# meter.net
KiCad netlist of a schematic drawn in EAGLE
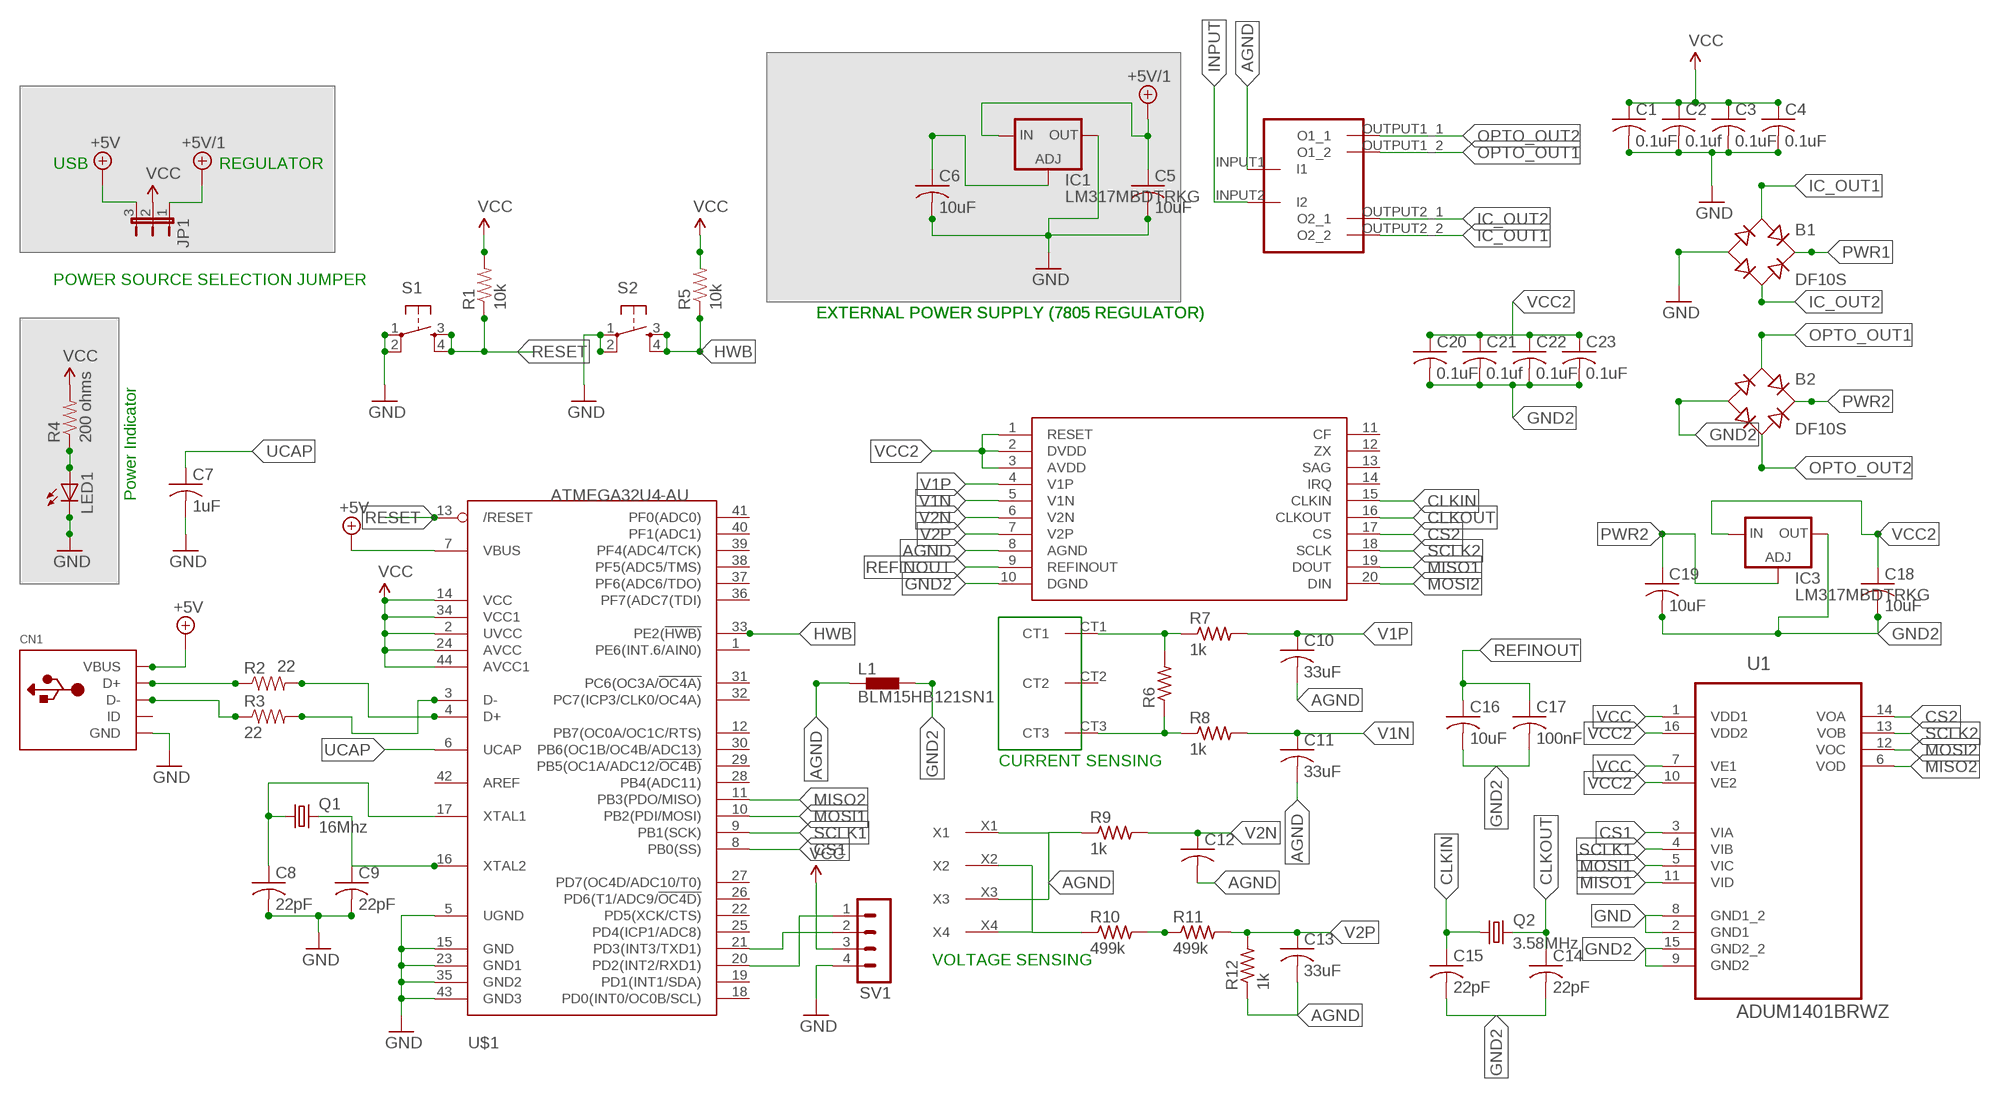
[diagram p0: schematic, sheet 1]

(export (version "E")
  (design (tool "Eeschema 10.0.6"))
  (components
    (comp (ref "B1")
      (value "DF10S")
      (footprint "eagle-import:DFS")
      (libsource (lib "eagle-import") (part "DFS10"))
    )
    (comp (ref "B2")
      (value "DF10S")
      (footprint "eagle-import:DFS")
      (libsource (lib "eagle-import") (part "DFS10"))
    )
    (comp (ref "C1")
      (value "0.1uF")
      (footprint "eagle-import:C0603")
      (libsource (lib "eagle-import") (part "C-USC0603"))
    )
    (comp (ref "C2")
      (value "0.1uf")
      (footprint "eagle-import:C0603")
      (libsource (lib "eagle-import") (part "C-USC0603"))
    )
    (comp (ref "C3")
      (value "0.1uF")
      (footprint "eagle-import:C0603")
      (libsource (lib "eagle-import") (part "C-USC0603"))
    )
    (comp (ref "C4")
      (value "0.1uF")
      (footprint "eagle-import:C0603")
      (libsource (lib "eagle-import") (part "C-USC0603"))
    )
    (comp (ref "C5")
      (value "10uF")
      (footprint "eagle-import:C0603")
      (libsource (lib "eagle-import") (part "C-USC0603"))
    )
    (comp (ref "C6")
      (value "10uF")
      (footprint "eagle-import:C0603")
      (libsource (lib "eagle-import") (part "C-USC0603"))
    )
    (comp (ref "C7")
      (value "1uF")
      (footprint "eagle-import:C0603")
      (libsource (lib "eagle-import") (part "C-USC0603"))
    )
    (comp (ref "C8")
      (value "22pF")
      (footprint "eagle-import:C0603")
      (libsource (lib "eagle-import") (part "C-USC0603"))
    )
    (comp (ref "C9")
      (value "22pF")
      (footprint "eagle-import:C0603")
      (libsource (lib "eagle-import") (part "C-USC0603"))
    )
    (comp (ref "C10")
      (value "33uF")
      (footprint "eagle-import:C0603")
      (libsource (lib "eagle-import") (part "C-USC0603"))
    )
    (comp (ref "C11")
      (value "33uF")
      (footprint "eagle-import:C0603")
      (libsource (lib "eagle-import") (part "C-USC0603"))
    )
    (comp (ref "C12")
      (value "C-USC0603")
      (footprint "eagle-import:C0603")
      (libsource (lib "eagle-import") (part "C-USC0603"))
    )
    (comp (ref "C13")
      (value "33uF")
      (footprint "eagle-import:C0603")
      (libsource (lib "eagle-import") (part "C-USC0603"))
    )
    (comp (ref "C14")
      (value "22pF")
      (footprint "eagle-import:C0603")
      (libsource (lib "eagle-import") (part "C-USC0603"))
    )
    (comp (ref "C15")
      (value "22pF")
      (footprint "eagle-import:C0603")
      (libsource (lib "eagle-import") (part "C-USC0603"))
    )
    (comp (ref "C16")
      (value "10uF")
      (footprint "eagle-import:C0603")
      (libsource (lib "eagle-import") (part "C-USC0603"))
    )
    (comp (ref "C17")
      (value "100nF")
      (footprint "eagle-import:C0603")
      (libsource (lib "eagle-import") (part "C-USC0603"))
    )
    (comp (ref "C18")
      (value "10uF")
      (footprint "eagle-import:C0603")
      (libsource (lib "eagle-import") (part "C-USC0603"))
    )
    (comp (ref "C19")
      (value "10uF")
      (footprint "eagle-import:C0603")
      (libsource (lib "eagle-import") (part "C-USC0603"))
    )
    (comp (ref "C20")
      (value "0.1uF")
      (footprint "eagle-import:C0603")
      (libsource (lib "eagle-import") (part "C-USC0603"))
    )
    (comp (ref "C21")
      (value "0.1uf")
      (footprint "eagle-import:C0603")
      (libsource (lib "eagle-import") (part "C-USC0603"))
    )
    (comp (ref "C22")
      (value "0.1uF")
      (footprint "eagle-import:C0603")
      (libsource (lib "eagle-import") (part "C-USC0603"))
    )
    (comp (ref "C23")
      (value "0.1uF")
      (footprint "eagle-import:C0603")
      (libsource (lib "eagle-import") (part "C-USC0603"))
    )
    (comp (ref "CN1")
      (value "USBMINIB")
      (footprint "eagle-import:USB-MINIB")
      (libsource (lib "eagle-import") (part "USBMINIB"))
    )
    (comp (ref "IC1")
      (value "LM317MBDTRKG")
      (footprint "eagle-import:DPACK")
      (libsource (lib "eagle-import") (part "LM317?MBDTRKG"))
    )
    (comp (ref "IC3")
      (value "LM317MBDTRKG")
      (footprint "eagle-import:DPACK")
      (libsource (lib "eagle-import") (part "LM317?MBDTRKG"))
    )
    (comp (ref "JP1")
      (value "JP2E")
      (footprint "eagle-import:JP2")
      (libsource (lib "eagle-import") (part "JP2E"))
    )
    (comp (ref "L1")
      (value "BLM15HB121SN1")
      (footprint "eagle-import:0402")
      (libsource (lib "eagle-import") (part "BLM15HB121SN1"))
    )
    (comp (ref "LED1")
      (value "LEDCHIP-LED0805")
      (footprint "eagle-import:CHIP-LED0805")
      (libsource (lib "eagle-import") (part "LEDCHIP-LED0805"))
    )
    (comp (ref "Q1")
      (value "16Mhz")
      (footprint "eagle-import:CSM-7X-DU")
      (libsource (lib "eagle-import") (part "CSM-7X-DU"))
    )
    (comp (ref "Q2")
      (value "3.58MHz")
      (footprint "eagle-import:CSM-7X-DU")
      (libsource (lib "eagle-import") (part "CSM-7X-DU"))
    )
    (comp (ref "R1")
      (value "10k")
      (footprint "eagle-import:0603-RES")
      (libsource (lib "eagle-import") (part "RESISTOR0603-RES"))
    )
    (comp (ref "R2")
      (value "22")
      (footprint "eagle-import:0603-RES")
      (libsource (lib "eagle-import") (part "RESISTOR0603-RES"))
    )
    (comp (ref "R3")
      (value "22")
      (footprint "eagle-import:0603-RES")
      (libsource (lib "eagle-import") (part "RESISTOR0603-RES"))
    )
    (comp (ref "R4")
      (value "200 ohms")
      (footprint "eagle-import:0603-RES")
      (libsource (lib "eagle-import") (part "RESISTOR0603-RES"))
    )
    (comp (ref "R5")
      (value "10k")
      (footprint "eagle-import:0603-RES")
      (libsource (lib "eagle-import") (part "RESISTOR0603-RES"))
    )
    (comp (ref "R6")
      (value "R-US_R0603")
      (footprint "eagle-import:R0603")
      (libsource (lib "eagle-import") (part "R-US_R0603"))
    )
    (comp (ref "R7")
      (value "1k")
      (footprint "eagle-import:R0603")
      (libsource (lib "eagle-import") (part "R-US_R0603"))
    )
    (comp (ref "R8")
      (value "1k")
      (footprint "eagle-import:R0603")
      (libsource (lib "eagle-import") (part "R-US_R0603"))
    )
    (comp (ref "R9")
      (value "1k")
      (footprint "eagle-import:R0603")
      (libsource (lib "eagle-import") (part "R-US_R0603"))
    )
    (comp (ref "R10")
      (value "499k")
      (footprint "eagle-import:R0603")
      (libsource (lib "eagle-import") (part "R-US_R0603"))
    )
    (comp (ref "R11")
      (value "499k")
      (footprint "eagle-import:R0603")
      (libsource (lib "eagle-import") (part "R-US_R0603"))
    )
    (comp (ref "R12")
      (value "1k")
      (footprint "eagle-import:R0603")
      (libsource (lib "eagle-import") (part "R-US_R0603"))
    )
    (comp (ref "S1")
      (value "TAC_SWITCHSMD")
      (footprint "eagle-import:TACTILE_SWITCH_SMD")
      (libsource (lib "eagle-import") (part "TAC_SWITCHSMD"))
    )
    (comp (ref "S2")
      (value "TAC_SWITCHSMD")
      (footprint "eagle-import:TACTILE_SWITCH_SMD")
      (libsource (lib "eagle-import") (part "TAC_SWITCHSMD"))
    )
    (comp (ref "SV1")
      (value "MA04-1")
      (footprint "eagle-import:MA04-1")
      (libsource (lib "eagle-import") (part "MA04-1"))
    )
    (comp (ref "U$1")
      (value "ATMEGA32U4-AU")
      (footprint "eagle-import:TQFP44")
      (libsource (lib "eagle-import") (part "ATMEGA32U4-AU"))
    )
    (comp (ref "U$2")
      (value "ADE7753")
      (footprint "eagle-import:SSOP20")
      (libsource (lib "eagle-import") (part "ADE7753"))
    )
    (comp (ref "U$3")
      (value "CT")
      (footprint "eagle-import:CT1075")
      (libsource (lib "eagle-import") (part "CT"))
    )
    (comp (ref "U$4")
      (value "PCB-TRANS")
      (footprint "eagle-import:PCB-TRANS")
      (libsource (lib "eagle-import") (part "PCB-TRANS"))
    )
    (comp (ref "U$6")
      (value "SCREWTERMINAL4_9.53")
      (footprint "eagle-import:SCREWTERMINAL4_9.53")
      (libsource (lib "eagle-import") (part "SCREWTERMINAL4_9.53"))
    )
    (comp (ref "U1")
      (value "ADUM1401BRWZ")
      (footprint "eagle-import:SOIC127P1032X265-16N")
      (libsource (lib "eagle-import") (part "ADUM1401BRWZ"))
    )
  )
  (nets
    (net (code "1") (name "+5V") (class "Default")
      (node (ref "CN1") (pin "VBUS") (pinfunction "VBUS_VBUS") (pintype "power_in"))
      (node (ref "JP1") (pin "3") (pinfunction "3_3") (pintype "passive"))
      (node (ref "U$1") (pin "7") (pinfunction "VBUS_7") (pintype "bidirectional"))
    )
    (net (code "2") (name "+5V{slash}1") (class "Default")
      (node (ref "C5") (pin "1") (pinfunction "1_1") (pintype "passive"))
      (node (ref "IC1") (pin "3") (pinfunction "IN_3") (pintype "input"))
      (node (ref "JP1") (pin "1") (pinfunction "1_1") (pintype "passive"))
    )
    (net (code "3") (name "AGND") (class "Default")
      (node (ref "C10") (pin "2") (pinfunction "2_2") (pintype "passive"))
      (node (ref "C11") (pin "2") (pinfunction "2_2") (pintype "passive"))
      (node (ref "C12") (pin "2") (pinfunction "2_2") (pintype "passive"))
      (node (ref "C13") (pin "2") (pinfunction "2_2") (pintype "passive"))
      (node (ref "L1") (pin "1") (pinfunction "1_1") (pintype "passive"))
      (node (ref "R12") (pin "1") (pinfunction "1_1") (pintype "passive"))
      (node (ref "R9") (pin "1") (pinfunction "1_1") (pintype "passive"))
      (node (ref "U$2") (pin "8") (pinfunction "AGND_8") (pintype "bidirectional"))
      (node (ref "U$4") (pin "INPUT1") (pinfunction "I1_INPUT1") (pintype "bidirectional"))
      (node (ref "U$6") (pin "X1") (pinfunction "X1_X1") (pintype "bidirectional"))
      (node (ref "U$6") (pin "X3") (pinfunction "X3_X3") (pintype "bidirectional"))
    )
    (net (code "4") (name "CLKIN") (class "Default")
      (node (ref "C15") (pin "1") (pinfunction "1_1") (pintype "passive"))
      (node (ref "Q2") (pin "1") (pinfunction "1_1") (pintype "passive"))
      (node (ref "U$2") (pin "15") (pinfunction "CLKIN_15") (pintype "bidirectional"))
    )
    (net (code "5") (name "CLKOUT") (class "Default")
      (node (ref "C14") (pin "1") (pinfunction "1_1") (pintype "passive"))
      (node (ref "Q2") (pin "2") (pinfunction "2_2") (pintype "passive"))
      (node (ref "U$2") (pin "16") (pinfunction "CLKOUT_16") (pintype "bidirectional"))
    )
    (net (code "6") (name "CS1") (class "Default")
      (node (ref "U$1") (pin "8") (pinfunction "PB0(SS)_8") (pintype "bidirectional"))
      (node (ref "U1") (pin "3") (pinfunction "VIA_3") (pintype "input"))
    )
    (net (code "7") (name "CS2") (class "Default")
      (node (ref "U$2") (pin "17") (pinfunction "CS_17") (pintype "bidirectional"))
      (node (ref "U1") (pin "14") (pinfunction "VOA_14") (pintype "output"))
    )
    (net (code "8") (name "GND") (class "Default")
      (node (ref "B1") (pin "-") (pinfunction "-_-") (pintype "passive"))
      (node (ref "C1") (pin "2") (pinfunction "2_2") (pintype "passive"))
      (node (ref "C2") (pin "2") (pinfunction "2_2") (pintype "passive"))
      (node (ref "C3") (pin "2") (pinfunction "2_2") (pintype "passive"))
      (node (ref "C4") (pin "2") (pinfunction "2_2") (pintype "passive"))
      (node (ref "C5") (pin "2") (pinfunction "2_2") (pintype "passive"))
      (node (ref "C6") (pin "2") (pinfunction "2_2") (pintype "passive"))
      (node (ref "C7") (pin "2") (pinfunction "2_2") (pintype "passive"))
      (node (ref "C8") (pin "2") (pinfunction "2_2") (pintype "passive"))
      (node (ref "C9") (pin "2") (pinfunction "2_2") (pintype "passive"))
      (node (ref "CN1") (pin "GND") (pinfunction "GND_GND") (pintype "power_in"))
      (node (ref "IC1") (pin "4") (pinfunction "OUT_4") (pintype "passive"))
      (node (ref "LED1") (pin "C") (pinfunction "C_C") (pintype "passive"))
      (node (ref "S1") (pin "1") (pinfunction "1_1") (pintype "passive"))
      (node (ref "S1") (pin "2") (pinfunction "2_2") (pintype "passive"))
      (node (ref "S2") (pin "1") (pinfunction "1_1") (pintype "passive"))
      (node (ref "S2") (pin "2") (pinfunction "2_2") (pintype "passive"))
      (node (ref "SV1") (pin "4") (pinfunction "4_4") (pintype "passive"))
      (node (ref "U$1") (pin "15") (pinfunction "GND_15") (pintype "bidirectional"))
      (node (ref "U$1") (pin "23") (pinfunction "GND1_23") (pintype "bidirectional"))
      (node (ref "U$1") (pin "35") (pinfunction "GND2_35") (pintype "bidirectional"))
      (node (ref "U$1") (pin "43") (pinfunction "GND3_43") (pintype "bidirectional"))
      (node (ref "U$1") (pin "5") (pinfunction "UGND_5") (pintype "bidirectional"))
      (node (ref "U1") (pin "2") (pinfunction "GND1_2") (pintype "passive"))
      (node (ref "U1") (pin "8") (pinfunction "GND1_2_8") (pintype "passive"))
    )
    (net (code "9") (name "GND2") (class "Default")
      (node (ref "B2") (pin "-") (pinfunction "-_-") (pintype "passive"))
      (node (ref "C14") (pin "2") (pinfunction "2_2") (pintype "passive"))
      (node (ref "C15") (pin "2") (pinfunction "2_2") (pintype "passive"))
      (node (ref "C16") (pin "2") (pinfunction "2_2") (pintype "passive"))
      (node (ref "C17") (pin "2") (pinfunction "2_2") (pintype "passive"))
      (node (ref "C18") (pin "2") (pinfunction "2_2") (pintype "passive"))
      (node (ref "C19") (pin "2") (pinfunction "2_2") (pintype "passive"))
      (node (ref "C20") (pin "2") (pinfunction "2_2") (pintype "passive"))
      (node (ref "C21") (pin "2") (pinfunction "2_2") (pintype "passive"))
      (node (ref "C22") (pin "2") (pinfunction "2_2") (pintype "passive"))
      (node (ref "C23") (pin "2") (pinfunction "2_2") (pintype "passive"))
      (node (ref "IC3") (pin "4") (pinfunction "OUT_4") (pintype "passive"))
      (node (ref "L1") (pin "2") (pinfunction "2_2") (pintype "passive"))
      (node (ref "U$2") (pin "10") (pinfunction "DGND_10") (pintype "bidirectional"))
      (node (ref "U1") (pin "15") (pinfunction "GND2_2_15") (pintype "passive"))
      (node (ref "U1") (pin "9") (pinfunction "GND2_9") (pintype "passive"))
    )
    (net (code "10") (name "HWB") (class "Default")
      (node (ref "R5") (pin "1") (pinfunction "1_1") (pintype "passive"))
      (node (ref "S2") (pin "3") (pinfunction "3_3") (pintype "passive"))
      (node (ref "S2") (pin "4") (pinfunction "4_4") (pintype "passive"))
      (node (ref "U$1") (pin "33") (pinfunction "PE2(~{HWB})_33") (pintype "bidirectional"))
    )
    (net (code "11") (name "IC_OUT1") (class "Default")
      (node (ref "B1") (pin "AC1") (pinfunction "AC1_AC1") (pintype "passive"))
      (node (ref "U$4") (pin "OUTPUT2_2") (pinfunction "O2_2_OUTPUT2_2") (pintype "bidirectional"))
    )
    (net (code "12") (name "IC_OUT2") (class "Default")
      (node (ref "B1") (pin "AC2") (pinfunction "AC2_AC2") (pintype "passive"))
      (node (ref "U$4") (pin "OUTPUT2_1") (pinfunction "O2_1_OUTPUT2_1") (pintype "bidirectional"))
    )
    (net (code "13") (name "INPUT") (class "Default")
      (node (ref "R10") (pin "1") (pinfunction "1_1") (pintype "passive"))
      (node (ref "U$4") (pin "INPUT2") (pinfunction "I2_INPUT2") (pintype "bidirectional"))
      (node (ref "U$6") (pin "X2") (pinfunction "X2_X2") (pintype "bidirectional"))
      (node (ref "U$6") (pin "X4") (pinfunction "X4_X4") (pintype "bidirectional"))
    )
    (net (code "14") (name "MISO1") (class "Default")
      (node (ref "U$2") (pin "19") (pinfunction "DOUT_19") (pintype "bidirectional"))
      (node (ref "U1") (pin "11") (pinfunction "VID_11") (pintype "input"))
    )
    (net (code "15") (name "MISO2") (class "Default")
      (node (ref "U$1") (pin "11") (pinfunction "PB3(PDO/MISO)_11") (pintype "bidirectional"))
      (node (ref "U1") (pin "6") (pinfunction "VOD_6") (pintype "output"))
    )
    (net (code "16") (name "MOSI1") (class "Default")
      (node (ref "U$1") (pin "10") (pinfunction "PB2(PDI/MOSI)_10") (pintype "bidirectional"))
      (node (ref "U1") (pin "5") (pinfunction "VIC_5") (pintype "input"))
    )
    (net (code "17") (name "MOSI2") (class "Default")
      (node (ref "U$2") (pin "20") (pinfunction "DIN_20") (pintype "bidirectional"))
      (node (ref "U1") (pin "12") (pinfunction "VOC_12") (pintype "output"))
    )
    (net (code "18") (name "Net-(CN1-PadD+)") (class "Default")
      (node (ref "CN1") (pin "D+") (pinfunction "D+_D+") (pintype "bidirectional"))
      (node (ref "R2") (pin "1") (pinfunction "1_1") (pintype "passive"))
    )
    (net (code "19") (name "Net-(CN1-PadD-)") (class "Default")
      (node (ref "CN1") (pin "D-") (pinfunction "D-_D-") (pintype "bidirectional"))
      (node (ref "R3") (pin "1") (pinfunction "1_1") (pintype "passive"))
    )
    (net (code "20") (name "Net-(LED1-PadA)") (class "Default")
      (node (ref "LED1") (pin "A") (pinfunction "A_A") (pintype "passive"))
      (node (ref "R4") (pin "1") (pinfunction "1_1") (pintype "passive"))
    )
    (net (code "21") (name "Net-(R6-Pad1)") (class "Default")
      (node (ref "R6") (pin "1") (pinfunction "1_1") (pintype "passive"))
      (node (ref "R8") (pin "1") (pinfunction "1_1") (pintype "passive"))
      (node (ref "U$3") (pin "CT3") (pinfunction "CT3_CT3") (pintype "bidirectional"))
    )
    (net (code "22") (name "Net-(R6-Pad2)") (class "Default")
      (node (ref "R6") (pin "2") (pinfunction "2_2") (pintype "passive"))
      (node (ref "R7") (pin "1") (pinfunction "1_1") (pintype "passive"))
      (node (ref "U$3") (pin "CT1") (pinfunction "CT1_CT1") (pintype "bidirectional"))
    )
    (net (code "23") (name "Net-(R10-Pad2)") (class "Default")
      (node (ref "R10") (pin "2") (pinfunction "2_2") (pintype "passive"))
      (node (ref "R11") (pin "1") (pinfunction "1_1") (pintype "passive"))
    )
    (net (code "24") (name "Net-(U$1-D+)") (class "Default")
      (node (ref "R2") (pin "2") (pinfunction "2_2") (pintype "passive"))
      (node (ref "U$1") (pin "4") (pinfunction "D+_4") (pintype "bidirectional"))
    )
    (net (code "25") (name "Net-(U$1-D-)") (class "Default")
      (node (ref "R3") (pin "2") (pinfunction "2_2") (pintype "passive"))
      (node (ref "U$1") (pin "3") (pinfunction "D-_3") (pintype "bidirectional"))
    )
    (net (code "26") (name "Net-(U$1-PD2(INT2{slash}RXD1))") (class "Default")
      (node (ref "SV1") (pin "1") (pinfunction "1_1") (pintype "passive"))
      (node (ref "U$1") (pin "20") (pinfunction "PD2(INT2/RXD1)_20") (pintype "bidirectional"))
    )
    (net (code "27") (name "Net-(U$1-PD3(INT3{slash}TXD1))") (class "Default")
      (node (ref "SV1") (pin "2") (pinfunction "2_2") (pintype "passive"))
      (node (ref "U$1") (pin "21") (pinfunction "PD3(INT3/TXD1)_21") (pintype "bidirectional"))
    )
    (net (code "28") (name "Net-(U$1-XTAL1)") (class "Default")
      (node (ref "C8") (pin "1") (pinfunction "1_1") (pintype "passive"))
      (node (ref "Q1") (pin "1") (pinfunction "1_1") (pintype "passive"))
      (node (ref "U$1") (pin "17") (pinfunction "XTAL1_17") (pintype "bidirectional"))
    )
    (net (code "29") (name "Net-(U$1-XTAL2)") (class "Default")
      (node (ref "C9") (pin "1") (pinfunction "1_1") (pintype "passive"))
      (node (ref "Q1") (pin "2") (pinfunction "2_2") (pintype "passive"))
      (node (ref "U$1") (pin "16") (pinfunction "XTAL2_16") (pintype "bidirectional"))
    )
    (net (code "30") (name "OPTO_OUT1") (class "Default")
      (node (ref "B2") (pin "AC1") (pinfunction "AC1_AC1") (pintype "passive"))
      (node (ref "U$4") (pin "OUTPUT1_2") (pinfunction "O1_2_OUTPUT1_2") (pintype "bidirectional"))
    )
    (net (code "31") (name "OPTO_OUT2") (class "Default")
      (node (ref "B2") (pin "AC2") (pinfunction "AC2_AC2") (pintype "passive"))
      (node (ref "U$4") (pin "OUTPUT1_1") (pinfunction "O1_1_OUTPUT1_1") (pintype "bidirectional"))
    )
    (net (code "32") (name "PWR1") (class "Default")
      (node (ref "B1") (pin "+") (pinfunction "+_+") (pintype "passive"))
      (node (ref "C6") (pin "1") (pinfunction "1_1") (pintype "passive"))
      (node (ref "IC1") (pin "1") (pinfunction "ADJ_1") (pintype "input"))
    )
    (net (code "33") (name "PWR2") (class "Default")
      (node (ref "B2") (pin "+") (pinfunction "+_+") (pintype "passive"))
      (node (ref "C19") (pin "1") (pinfunction "1_1") (pintype "passive"))
      (node (ref "IC3") (pin "1") (pinfunction "ADJ_1") (pintype "input"))
    )
    (net (code "34") (name "REFINOUT") (class "Default")
      (node (ref "C16") (pin "1") (pinfunction "1_1") (pintype "passive"))
      (node (ref "C17") (pin "1") (pinfunction "1_1") (pintype "passive"))
      (node (ref "U$2") (pin "9") (pinfunction "REFINOUT_9") (pintype "bidirectional"))
    )
    (net (code "35") (name "RESET") (class "Default")
      (node (ref "R1") (pin "1") (pinfunction "1_1") (pintype "passive"))
      (node (ref "S1") (pin "3") (pinfunction "3_3") (pintype "passive"))
      (node (ref "S1") (pin "4") (pinfunction "4_4") (pintype "passive"))
      (node (ref "U$1") (pin "13") (pinfunction "/RESET_13") (pintype "bidirectional"))
    )
    (net (code "36") (name "SCLK1") (class "Default")
      (node (ref "U$1") (pin "9") (pinfunction "PB1(SCK)_9") (pintype "bidirectional"))
      (node (ref "U1") (pin "4") (pinfunction "VIB_4") (pintype "input"))
    )
    (net (code "37") (name "SCLK2") (class "Default")
      (node (ref "U$2") (pin "18") (pinfunction "SCLK_18") (pintype "bidirectional"))
      (node (ref "U1") (pin "13") (pinfunction "VOB_13") (pintype "output"))
    )
    (net (code "38") (name "UCAP") (class "Default")
      (node (ref "C7") (pin "1") (pinfunction "1_1") (pintype "passive"))
      (node (ref "U$1") (pin "6") (pinfunction "UCAP_6") (pintype "bidirectional"))
    )
    (net (code "39") (name "V1N") (class "Default")
      (node (ref "C11") (pin "1") (pinfunction "1_1") (pintype "passive"))
      (node (ref "R8") (pin "2") (pinfunction "2_2") (pintype "passive"))
      (node (ref "U$2") (pin "5") (pinfunction "V1N_5") (pintype "bidirectional"))
    )
    (net (code "40") (name "V1P") (class "Default")
      (node (ref "C10") (pin "1") (pinfunction "1_1") (pintype "passive"))
      (node (ref "R7") (pin "2") (pinfunction "2_2") (pintype "passive"))
      (node (ref "U$2") (pin "4") (pinfunction "V1P_4") (pintype "bidirectional"))
    )
    (net (code "41") (name "V2N") (class "Default")
      (node (ref "C12") (pin "1") (pinfunction "1_1") (pintype "passive"))
      (node (ref "R9") (pin "2") (pinfunction "2_2") (pintype "passive"))
      (node (ref "U$2") (pin "6") (pinfunction "V2N_6") (pintype "bidirectional"))
    )
    (net (code "42") (name "V2P") (class "Default")
      (node (ref "C13") (pin "1") (pinfunction "1_1") (pintype "passive"))
      (node (ref "R11") (pin "2") (pinfunction "2_2") (pintype "passive"))
      (node (ref "R12") (pin "2") (pinfunction "2_2") (pintype "passive"))
      (node (ref "U$2") (pin "7") (pinfunction "V2P_7") (pintype "bidirectional"))
    )
    (net (code "43") (name "VCC") (class "Default")
      (node (ref "C1") (pin "1") (pinfunction "1_1") (pintype "passive"))
      (node (ref "C2") (pin "1") (pinfunction "1_1") (pintype "passive"))
      (node (ref "C3") (pin "1") (pinfunction "1_1") (pintype "passive"))
      (node (ref "C4") (pin "1") (pinfunction "1_1") (pintype "passive"))
      (node (ref "JP1") (pin "2") (pinfunction "2_2") (pintype "passive"))
      (node (ref "R1") (pin "2") (pinfunction "2_2") (pintype "passive"))
      (node (ref "R4") (pin "2") (pinfunction "2_2") (pintype "passive"))
      (node (ref "R5") (pin "2") (pinfunction "2_2") (pintype "passive"))
      (node (ref "SV1") (pin "3") (pinfunction "3_3") (pintype "passive"))
      (node (ref "U$1") (pin "14") (pinfunction "VCC_14") (pintype "bidirectional"))
      (node (ref "U$1") (pin "2") (pinfunction "UVCC_2") (pintype "bidirectional"))
      (node (ref "U$1") (pin "24") (pinfunction "AVCC_24") (pintype "bidirectional"))
      (node (ref "U$1") (pin "34") (pinfunction "VCC1_34") (pintype "bidirectional"))
      (node (ref "U$1") (pin "44") (pinfunction "AVCC1_44") (pintype "bidirectional"))
      (node (ref "U1") (pin "1") (pinfunction "VDD1_1") (pintype "power_in"))
      (node (ref "U1") (pin "7") (pinfunction "VE1_7") (pintype "input"))
    )
    (net (code "44") (name "VCC2") (class "Default")
      (node (ref "C18") (pin "1") (pinfunction "1_1") (pintype "passive"))
      (node (ref "C20") (pin "1") (pinfunction "1_1") (pintype "passive"))
      (node (ref "C21") (pin "1") (pinfunction "1_1") (pintype "passive"))
      (node (ref "C22") (pin "1") (pinfunction "1_1") (pintype "passive"))
      (node (ref "C23") (pin "1") (pinfunction "1_1") (pintype "passive"))
      (node (ref "IC3") (pin "3") (pinfunction "IN_3") (pintype "input"))
      (node (ref "U$2") (pin "1") (pinfunction "RESET_1") (pintype "bidirectional"))
      (node (ref "U$2") (pin "2") (pinfunction "DVDD_2") (pintype "bidirectional"))
      (node (ref "U$2") (pin "3") (pinfunction "AVDD_3") (pintype "bidirectional"))
      (node (ref "U1") (pin "10") (pinfunction "VE2_10") (pintype "input"))
      (node (ref "U1") (pin "16") (pinfunction "VDD2_16") (pintype "power_in"))
    )
    (net (code "45") (name "unconnected-(CN1-PadID)") (class "Default")
      (node (ref "CN1") (pin "ID") (pinfunction "ID_ID") (pintype "bidirectional"))
    )
    (net (code "46") (name "unconnected-(U$1-AREF-Pad42)") (class "Default")
      (node (ref "U$1") (pin "42") (pinfunction "AREF_42") (pintype "bidirectional"))
    )
    (net (code "47") (name "unconnected-(U$1-PB4(ADC11)-Pad28)") (class "Default")
      (node (ref "U$1") (pin "28") (pinfunction "PB4(ADC11)_28") (pintype "bidirectional"))
    )
    (net (code "48") (name "unconnected-(U$1-PB5(OC1A{slash}ADC12{slash}~{OC4B})-Pad29)") (class "Default")
      (node (ref "U$1") (pin "29") (pinfunction "PB5(OC1A/ADC12/~{OC4B})_29") (pintype "bidirectional"))
    )
    (net (code "49") (name "unconnected-(U$1-PB6(OC1B{slash}OC4B{slash}ADC13)-Pad30)") (class "Default")
      (node (ref "U$1") (pin "30") (pinfunction "PB6(OC1B/OC4B/ADC13)_30") (pintype "bidirectional"))
    )
    (net (code "50") (name "unconnected-(U$1-PB7(OC0A{slash}OC1C{slash}RTS)-Pad12)") (class "Default")
      (node (ref "U$1") (pin "12") (pinfunction "PB7(OC0A/OC1C/RTS)_12") (pintype "bidirectional"))
    )
    (net (code "51") (name "unconnected-(U$1-PC6(OC3A{slash}~{OC4A})-Pad31)") (class "Default")
      (node (ref "U$1") (pin "31") (pinfunction "PC6(OC3A/~{OC4A})_31") (pintype "bidirectional"))
    )
    (net (code "52") (name "unconnected-(U$1-PC7(ICP3{slash}CLK0{slash}OC4A)-Pad32)") (class "Default")
      (node (ref "U$1") (pin "32") (pinfunction "PC7(ICP3/CLK0/OC4A)_32") (pintype "bidirectional"))
    )
    (net (code "53") (name "unconnected-(U$1-PD0(INT0{slash}OC0B{slash}SCL)-Pad18)") (class "Default")
      (node (ref "U$1") (pin "18") (pinfunction "PD0(INT0/OC0B/SCL)_18") (pintype "bidirectional"))
    )
    (net (code "54") (name "unconnected-(U$1-PD1(INT1{slash}SDA)-Pad19)") (class "Default")
      (node (ref "U$1") (pin "19") (pinfunction "PD1(INT1/SDA)_19") (pintype "bidirectional"))
    )
    (net (code "55") (name "unconnected-(U$1-PD4(ICP1{slash}ADC8)-Pad25)") (class "Default")
      (node (ref "U$1") (pin "25") (pinfunction "PD4(ICP1/ADC8)_25") (pintype "bidirectional"))
    )
    (net (code "56") (name "unconnected-(U$1-PD5(XCK{slash}CTS)-Pad22)") (class "Default")
      (node (ref "U$1") (pin "22") (pinfunction "PD5(XCK/CTS)_22") (pintype "bidirectional"))
    )
    (net (code "57") (name "unconnected-(U$1-PD6(T1{slash}ADC9{slash}~{OC4D})-Pad26)") (class "Default")
      (node (ref "U$1") (pin "26") (pinfunction "PD6(T1/ADC9/~{OC4D})_26") (pintype "bidirectional"))
    )
    (net (code "58") (name "unconnected-(U$1-PD7(OC4D{slash}ADC10{slash}T0)-Pad27)") (class "Default")
      (node (ref "U$1") (pin "27") (pinfunction "PD7(OC4D/ADC10/T0)_27") (pintype "bidirectional"))
    )
    (net (code "59") (name "unconnected-(U$1-PE6(INT.6{slash}AIN0)-Pad1)") (class "Default")
      (node (ref "U$1") (pin "1") (pinfunction "PE6(INT.6/AIN0)_1") (pintype "bidirectional"))
    )
    (net (code "60") (name "unconnected-(U$1-PF0(ADC0)-Pad41)") (class "Default")
      (node (ref "U$1") (pin "41") (pinfunction "PF0(ADC0)_41") (pintype "bidirectional"))
    )
    (net (code "61") (name "unconnected-(U$1-PF1(ADC1)-Pad40)") (class "Default")
      (node (ref "U$1") (pin "40") (pinfunction "PF1(ADC1)_40") (pintype "bidirectional"))
    )
    (net (code "62") (name "unconnected-(U$1-PF4(ADC4{slash}TCK)-Pad39)") (class "Default")
      (node (ref "U$1") (pin "39") (pinfunction "PF4(ADC4/TCK)_39") (pintype "bidirectional"))
    )
    (net (code "63") (name "unconnected-(U$1-PF5(ADC5{slash}TMS)-Pad38)") (class "Default")
      (node (ref "U$1") (pin "38") (pinfunction "PF5(ADC5/TMS)_38") (pintype "bidirectional"))
    )
    (net (code "64") (name "unconnected-(U$1-PF6(ADC6{slash}TDO)-Pad37)") (class "Default")
      (node (ref "U$1") (pin "37") (pinfunction "PF6(ADC6/TDO)_37") (pintype "bidirectional"))
    )
    (net (code "65") (name "unconnected-(U$1-PF7(ADC7(TDI)-Pad36)") (class "Default")
      (node (ref "U$1") (pin "36") (pinfunction "PF7(ADC7(TDI)_36") (pintype "bidirectional"))
    )
    (net (code "66") (name "unconnected-(U$2-CF-Pad11)") (class "Default")
      (node (ref "U$2") (pin "11") (pinfunction "CF_11") (pintype "bidirectional"))
    )
    (net (code "67") (name "unconnected-(U$2-IRQ-Pad14)") (class "Default")
      (node (ref "U$2") (pin "14") (pinfunction "IRQ_14") (pintype "bidirectional"))
    )
    (net (code "68") (name "unconnected-(U$2-SAG-Pad13)") (class "Default")
      (node (ref "U$2") (pin "13") (pinfunction "SAG_13") (pintype "bidirectional"))
    )
    (net (code "69") (name "unconnected-(U$2-ZX-Pad12)") (class "Default")
      (node (ref "U$2") (pin "12") (pinfunction "ZX_12") (pintype "bidirectional"))
    )
    (net (code "70") (name "unconnected-(U$3-PadCT2)") (class "Default")
      (node (ref "U$3") (pin "CT2") (pinfunction "CT2_CT2") (pintype "bidirectional"))
    )
  )
)
